# KV10BLDCControl.net
KiCad netlist of a schematic drawn in Altium Designer
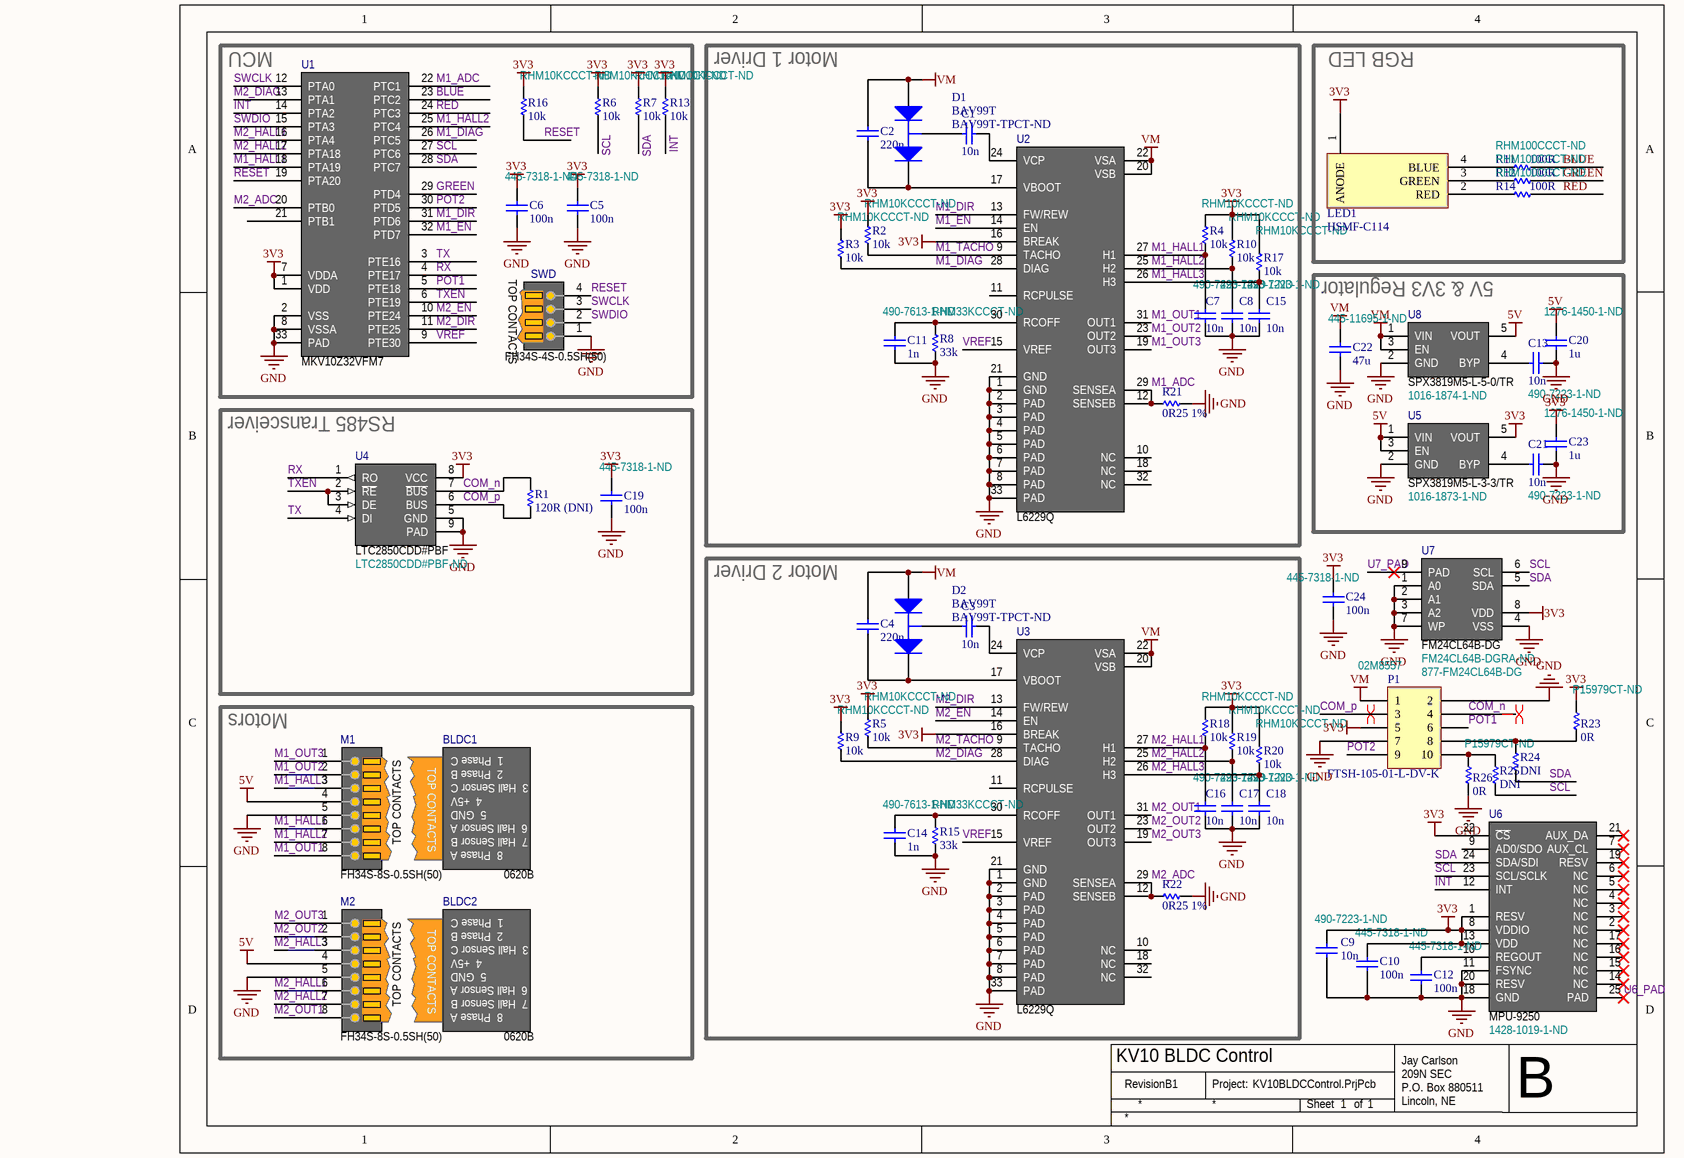
[diagram p0: KV10BLDCControl.SchDoc]

(export (version "E")
  (design (tool "Eeschema 10.0.6"))
  (components
    (comp (ref "BLDC1") (value "0620B") (libsource (lib "Faulhaber BLDC Motors") (part "0620B")))
    (comp (ref "BLDC2") (value "0620B") (libsource (lib "Faulhaber BLDC Motors") (part "0620B")))
    (comp (ref "C1")
      (value "10n")
      (footprint "CAPC1005N")
      (description "Capacitor (Semiconductor SIM Model)")
      (fields (field (name "PUBLISHER") "Altium Limited"))
      (libsource (lib "Miscellaneous Devices") (part "Cap Semi"))
    )
    (comp (ref "C2")
      (value "220n")
      (footprint "CAPC1005N")
      (description "Capacitor (Semiconductor SIM Model)")
      (fields (field (name "PUBLISHER") "Altium Limited"))
      (libsource (lib "Miscellaneous Devices") (part "Cap Semi"))
    )
    (comp (ref "C3")
      (value "10n")
      (footprint "CAPC1005N")
      (description "Capacitor (Semiconductor SIM Model)")
      (fields (field (name "PUBLISHER") "Altium Limited"))
      (libsource (lib "Miscellaneous Devices") (part "Cap Semi"))
    )
    (comp (ref "C4")
      (value "220n")
      (footprint "CAPC1005N")
      (description "Capacitor (Semiconductor SIM Model)")
      (fields (field (name "PUBLISHER") "Altium Limited"))
      (libsource (lib "Miscellaneous Devices") (part "Cap Semi"))
    )
    (comp (ref "C5")
      (value "100n")
      (footprint "CAPC0603N")
      (description "Capacitor (Semiconductor SIM Model)")
      (fields
        (field (name "SUPPLIER PART NUMBER 1") "445-7318-1-ND")
        (field (name "PUBLISHER") "Altium Limited")
      )
      (libsource (lib "Miscellaneous Devices") (part "Cap Semi"))
    )
    (comp (ref "C6")
      (value "100n")
      (footprint "CAPC0603N")
      (description "Capacitor (Semiconductor SIM Model)")
      (fields
        (field (name "SUPPLIER PART NUMBER 1") "445-7318-1-ND")
        (field (name "PUBLISHER") "Altium Limited")
      )
      (libsource (lib "Miscellaneous Devices") (part "Cap Semi"))
    )
    (comp (ref "C7")
      (value "10n")
      (footprint "CAPC0603N")
      (description "Capacitor (Semiconductor SIM Model)")
      (fields
        (field (name "SUPPLIER PART NUMBER 1") "490-7223-1-ND")
        (field (name "PUBLISHER") "Altium Limited")
      )
      (libsource (lib "Miscellaneous Devices") (part "Cap Semi"))
    )
    (comp (ref "C8")
      (value "10n")
      (footprint "CAPC0603N")
      (description "Capacitor (Semiconductor SIM Model)")
      (fields
        (field (name "SUPPLIER PART NUMBER 1") "490-7223-1-ND")
        (field (name "PUBLISHER") "Altium Limited")
      )
      (libsource (lib "Miscellaneous Devices") (part "Cap Semi"))
    )
    (comp (ref "C9")
      (value "10n")
      (footprint "CAPC0603N")
      (description "Capacitor (Semiconductor SIM Model)")
      (fields
        (field (name "SUPPLIER PART NUMBER 1") "490-7223-1-ND")
        (field (name "PUBLISHER") "Altium Limited")
      )
      (libsource (lib "Miscellaneous Devices") (part "Cap Semi"))
    )
    (comp (ref "C10")
      (value "100n")
      (footprint "CAPC0603N")
      (description "Capacitor (Semiconductor SIM Model)")
      (fields
        (field (name "SUPPLIER PART NUMBER 1") "445-7318-1-ND")
        (field (name "PUBLISHER") "Altium Limited")
      )
      (libsource (lib "Miscellaneous Devices") (part "Cap Semi"))
    )
    (comp (ref "C11")
      (value "1n")
      (footprint "CAPC0603N")
      (description "Capacitor (Semiconductor SIM Model)")
      (fields
        (field (name "SUPPLIER PART NUMBER 1") "490-7613-1-ND")
        (field (name "PUBLISHER") "Altium Limited")
      )
      (libsource (lib "Miscellaneous Devices") (part "Cap Semi"))
    )
    (comp (ref "C12")
      (value "100n")
      (footprint "CAPC0603N")
      (description "Capacitor (Semiconductor SIM Model)")
      (fields
        (field (name "SUPPLIER PART NUMBER 1") "445-7318-1-ND")
        (field (name "PUBLISHER") "Altium Limited")
      )
      (libsource (lib "Miscellaneous Devices") (part "Cap Semi"))
    )
    (comp (ref "C13")
      (value "10n")
      (footprint "CAPC0603N")
      (description "Capacitor (Semiconductor SIM Model)")
      (fields
        (field (name "SUPPLIER PART NUMBER 1") "490-7223-1-ND")
        (field (name "PUBLISHER") "Altium Limited")
      )
      (libsource (lib "Miscellaneous Devices") (part "Cap Semi"))
    )
    (comp (ref "C14")
      (value "1n")
      (footprint "CAPC0603N")
      (description "Capacitor (Semiconductor SIM Model)")
      (fields
        (field (name "SUPPLIER PART NUMBER 1") "490-7613-1-ND")
        (field (name "PUBLISHER") "Altium Limited")
      )
      (libsource (lib "Miscellaneous Devices") (part "Cap Semi"))
    )
    (comp (ref "C15")
      (value "10n")
      (footprint "CAPC0603N")
      (description "Capacitor (Semiconductor SIM Model)")
      (fields
        (field (name "SUPPLIER PART NUMBER 1") "490-7223-1-ND")
        (field (name "PUBLISHER") "Altium Limited")
      )
      (libsource (lib "Miscellaneous Devices") (part "Cap Semi"))
    )
    (comp (ref "C16")
      (value "10n")
      (footprint "CAPC0603N")
      (description "Capacitor (Semiconductor SIM Model)")
      (fields
        (field (name "SUPPLIER PART NUMBER 1") "490-7223-1-ND")
        (field (name "PUBLISHER") "Altium Limited")
      )
      (libsource (lib "Miscellaneous Devices") (part "Cap Semi"))
    )
    (comp (ref "C17")
      (value "10n")
      (footprint "CAPC0603N")
      (description "Capacitor (Semiconductor SIM Model)")
      (fields
        (field (name "SUPPLIER PART NUMBER 1") "490-7223-1-ND")
        (field (name "PUBLISHER") "Altium Limited")
      )
      (libsource (lib "Miscellaneous Devices") (part "Cap Semi"))
    )
    (comp (ref "C18")
      (value "10n")
      (footprint "CAPC0603N")
      (description "Capacitor (Semiconductor SIM Model)")
      (fields
        (field (name "SUPPLIER PART NUMBER 1") "490-7223-1-ND")
        (field (name "PUBLISHER") "Altium Limited")
      )
      (libsource (lib "Miscellaneous Devices") (part "Cap Semi"))
    )
    (comp (ref "C19")
      (value "100n")
      (footprint "CAPC0603N")
      (description "Capacitor (Semiconductor SIM Model)")
      (fields
        (field (name "SUPPLIER PART NUMBER 1") "445-7318-1-ND")
        (field (name "PUBLISHER") "Altium Limited")
      )
      (libsource (lib "Miscellaneous Devices") (part "Cap Semi"))
    )
    (comp (ref "C20")
      (value "1u")
      (footprint "CAPC1005N")
      (description "Capacitor (Semiconductor SIM Model)")
      (fields
        (field (name "SUPPLIER PART NUMBER 1") "1276-1450-1-ND")
        (field (name "PUBLISHER") "Altium Limited")
      )
      (libsource (lib "Miscellaneous Devices") (part "Cap Semi"))
    )
    (comp (ref "C21")
      (value "10n")
      (footprint "CAPC0603N")
      (description "Capacitor (Semiconductor SIM Model)")
      (fields
        (field (name "SUPPLIER PART NUMBER 1") "490-7223-1-ND")
        (field (name "PUBLISHER") "Altium Limited")
      )
      (libsource (lib "Miscellaneous Devices") (part "Cap Semi"))
    )
    (comp (ref "C22")
      (value "47u")
      (footprint "CAPC3216N")
      (description "Capacitor (Semiconductor SIM Model)")
      (fields
        (field (name "SUPPLIER PART NUMBER 1") "445-11695-1-ND")
        (field (name "PUBLISHER") "Altium Limited")
      )
      (libsource (lib "Miscellaneous Devices") (part "Cap Semi"))
    )
    (comp (ref "C23")
      (value "1u")
      (footprint "CAPC1005N")
      (description "Capacitor (Semiconductor SIM Model)")
      (fields
        (field (name "SUPPLIER PART NUMBER 1") "1276-1450-1-ND")
        (field (name "PUBLISHER") "Altium Limited")
      )
      (libsource (lib "Miscellaneous Devices") (part "Cap Semi"))
    )
    (comp (ref "C24")
      (value "100n")
      (footprint "CAPC0603N")
      (description "Capacitor (Semiconductor SIM Model)")
      (fields
        (field (name "SUPPLIER PART NUMBER 1") "445-7318-1-ND")
        (field (name "PUBLISHER") "Altium Limited")
      )
      (libsource (lib "Miscellaneous Devices") (part "Cap Semi"))
    )
    (comp (ref "D1")
      (value "BAV99T")
      (footprint "SOT-523 (SC-75)")
      (description "Silicon Switching Diode for High-Speed Switching")
      (fields
        (field (name "SUPPLIER PART NUMBER 1") "BAV99T-TPCT-ND")
        (field (name "PUBLISHER") "Altium Limited")
      )
      (libsource (lib "Infineon Discrete Diode") (part "BAV99T"))
    )
    (comp (ref "D2")
      (value "BAV99T")
      (footprint "SOT-523 (SC-75)")
      (description "Silicon Switching Diode for High-Speed Switching")
      (fields
        (field (name "SUPPLIER PART NUMBER 1") "BAV99T-TPCT-ND")
        (field (name "PUBLISHER") "Altium Limited")
      )
      (libsource (lib "Infineon Discrete Diode") (part "BAV99T"))
    )
    (comp (ref "LED1")
      (value "HSMF-C114")
      (footprint "HSMF-C114")
      (description "LED CHIP RGB 1.6X1.5X0.35MM SMD")
      (fields (field (name "MANUFACTURER") "Avago Technologies US Inc."))
      (libsource (lib "components") (part "HSMF-C114"))
    )
    (comp (ref "M1")
      (value "FH34S-8S-0.5SH(50)")
      (footprint "FH34S-8S-0.5SH(50)")
      (description "CONN FPC/FFC 8POS .5MM SMD GOLD")
      (fields (field (name "MANUFACTURER") "Hirose Electric Co Ltd"))
      (libsource (lib "FH34 series") (part "FH34S-8S-0.5SH(50)"))
    )
    (comp (ref "M2")
      (value "FH34S-8S-0.5SH(50)")
      (footprint "FH34S-8S-0.5SH(50)")
      (description "CONN FPC/FFC 8POS .5MM SMD GOLD")
      (fields (field (name "MANUFACTURER") "Hirose Electric Co Ltd"))
      (libsource (lib "FH34 series") (part "FH34S-8S-0.5SH(50)"))
    )
    (comp (ref "P1")
      (value "FTSH-105-01-L-DV-K")
      (footprint "FTSH-105-01-L-DV-K")
      (description "Header, 5-Pin, Dual row")
      (fields (field (name "SUPPLIER PART NUMBER 1") "02M8557") (field (name "PUBLISHER") "Altium Limited"))
      (libsource (lib "Miscellaneous Connectors") (part "MHDR2X5"))
    )
    (comp (ref "R1")
      (value "120R (DNI)")
      (footprint "RESC0603N")
      (description "Semiconductor Resistor")
      (fields (field (name "PUBLISHER") "Altium Limited"))
      (libsource (lib "Miscellaneous Devices") (part "Res Semi"))
    )
    (comp (ref "R2")
      (value "10k")
      (footprint "RESC0603N")
      (description "Semiconductor Resistor")
      (fields
        (field (name "SUPPLIER PART NUMBER 1") "RHM10KCCCT-ND")
        (field (name "PUBLISHER") "Altium Limited")
      )
      (libsource (lib "Miscellaneous Devices") (part "Res Semi"))
    )
    (comp (ref "R3")
      (value "10k")
      (footprint "RESC0603N")
      (description "Semiconductor Resistor")
      (fields
        (field (name "SUPPLIER PART NUMBER 1") "RHM10KCCCT-ND")
        (field (name "PUBLISHER") "Altium Limited")
      )
      (libsource (lib "Miscellaneous Devices") (part "Res Semi"))
    )
    (comp (ref "R4")
      (value "10k")
      (footprint "RESC0603N")
      (description "Semiconductor Resistor")
      (fields
        (field (name "SUPPLIER PART NUMBER 1") "RHM10KCCCT-ND")
        (field (name "PUBLISHER") "Altium Limited")
      )
      (libsource (lib "Miscellaneous Devices") (part "Res Semi"))
    )
    (comp (ref "R5")
      (value "10k")
      (footprint "RESC0603N")
      (description "Semiconductor Resistor")
      (fields
        (field (name "SUPPLIER PART NUMBER 1") "RHM10KCCCT-ND")
        (field (name "PUBLISHER") "Altium Limited")
      )
      (libsource (lib "Miscellaneous Devices") (part "Res Semi"))
    )
    (comp (ref "R6")
      (value "10k")
      (footprint "RESC0603N")
      (description "Semiconductor Resistor")
      (fields
        (field (name "SUPPLIER PART NUMBER 1") "RHM10KCCCT-ND")
        (field (name "PUBLISHER") "Altium Limited")
      )
      (libsource (lib "Miscellaneous Devices") (part "Res Semi"))
    )
    (comp (ref "R7")
      (value "10k")
      (footprint "RESC0603N")
      (description "Semiconductor Resistor")
      (fields
        (field (name "SUPPLIER PART NUMBER 1") "RHM10KCCCT-ND")
        (field (name "PUBLISHER") "Altium Limited")
      )
      (libsource (lib "Miscellaneous Devices") (part "Res Semi"))
    )
    (comp (ref "R8")
      (value "33k")
      (footprint "RESC0603N")
      (description "Semiconductor Resistor")
      (fields
        (field (name "SUPPLIER PART NUMBER 1") "RHM33KCCCT-ND")
        (field (name "PUBLISHER") "Altium Limited")
      )
      (libsource (lib "Miscellaneous Devices") (part "Res Semi"))
    )
    (comp (ref "R9")
      (value "10k")
      (footprint "RESC0603N")
      (description "Semiconductor Resistor")
      (fields
        (field (name "SUPPLIER PART NUMBER 1") "RHM10KCCCT-ND")
        (field (name "PUBLISHER") "Altium Limited")
      )
      (libsource (lib "Miscellaneous Devices") (part "Res Semi"))
    )
    (comp (ref "R10")
      (value "10k")
      (footprint "RESC0603N")
      (description "Semiconductor Resistor")
      (fields
        (field (name "SUPPLIER PART NUMBER 1") "RHM10KCCCT-ND")
        (field (name "PUBLISHER") "Altium Limited")
      )
      (libsource (lib "Miscellaneous Devices") (part "Res Semi"))
    )
    (comp (ref "R11")
      (value "100R")
      (footprint "RESC0603N")
      (description "Semiconductor Resistor")
      (fields
        (field (name "SUPPLIER PART NUMBER 1") "RHM100CCCT-ND")
        (field (name "PUBLISHER") "Altium Limited")
      )
      (libsource (lib "Miscellaneous Devices") (part "Res Semi"))
    )
    (comp (ref "R12")
      (value "100R")
      (footprint "RESC0603N")
      (description "Semiconductor Resistor")
      (fields
        (field (name "SUPPLIER PART NUMBER 1") "RHM100CCCT-ND")
        (field (name "PUBLISHER") "Altium Limited")
      )
      (libsource (lib "Miscellaneous Devices") (part "Res Semi"))
    )
    (comp (ref "R13")
      (value "10k")
      (footprint "RESC0603N")
      (description "Semiconductor Resistor")
      (fields
        (field (name "SUPPLIER PART NUMBER 1") "RHM10KCCCT-ND")
        (field (name "PUBLISHER") "Altium Limited")
      )
      (libsource (lib "Miscellaneous Devices") (part "Res Semi"))
    )
    (comp (ref "R14")
      (value "100R")
      (footprint "RESC0603N")
      (description "Semiconductor Resistor")
      (fields
        (field (name "SUPPLIER PART NUMBER 1") "RHM100CCCT-ND")
        (field (name "PUBLISHER") "Altium Limited")
      )
      (libsource (lib "Miscellaneous Devices") (part "Res Semi"))
    )
    (comp (ref "R15")
      (value "33k")
      (footprint "RESC0603N")
      (description "Semiconductor Resistor")
      (fields
        (field (name "SUPPLIER PART NUMBER 1") "RHM33KCCCT-ND")
        (field (name "PUBLISHER") "Altium Limited")
      )
      (libsource (lib "Miscellaneous Devices") (part "Res Semi"))
    )
    (comp (ref "R16")
      (value "10k")
      (footprint "RESC0603N")
      (description "Semiconductor Resistor")
      (fields
        (field (name "SUPPLIER PART NUMBER 1") "RHM10KCCCT-ND")
        (field (name "PUBLISHER") "Altium Limited")
      )
      (libsource (lib "Miscellaneous Devices") (part "Res Semi"))
    )
    (comp (ref "R17")
      (value "10k")
      (footprint "RESC0603N")
      (description "Semiconductor Resistor")
      (fields
        (field (name "SUPPLIER PART NUMBER 1") "RHM10KCCCT-ND")
        (field (name "PUBLISHER") "Altium Limited")
      )
      (libsource (lib "Miscellaneous Devices") (part "Res Semi"))
    )
    (comp (ref "R18")
      (value "10k")
      (footprint "RESC0603N")
      (description "Semiconductor Resistor")
      (fields
        (field (name "SUPPLIER PART NUMBER 1") "RHM10KCCCT-ND")
        (field (name "PUBLISHER") "Altium Limited")
      )
      (libsource (lib "Miscellaneous Devices") (part "Res Semi"))
    )
    (comp (ref "R19")
      (value "10k")
      (footprint "RESC0603N")
      (description "Semiconductor Resistor")
      (fields
        (field (name "SUPPLIER PART NUMBER 1") "RHM10KCCCT-ND")
        (field (name "PUBLISHER") "Altium Limited")
      )
      (libsource (lib "Miscellaneous Devices") (part "Res Semi"))
    )
    (comp (ref "R20")
      (value "10k")
      (footprint "RESC0603N")
      (description "Semiconductor Resistor")
      (fields
        (field (name "SUPPLIER PART NUMBER 1") "RHM10KCCCT-ND")
        (field (name "PUBLISHER") "Altium Limited")
      )
      (libsource (lib "Miscellaneous Devices") (part "Res Semi"))
    )
    (comp (ref "R21")
      (value "0R25 1%")
      (footprint "RESC1608N")
      (description "Semiconductor Resistor")
      (fields (field (name "PUBLISHER") "Altium Limited"))
      (libsource (lib "Miscellaneous Devices") (part "Res Semi"))
    )
    (comp (ref "R22")
      (value "0R25 1%")
      (footprint "RESC1608N")
      (description "Semiconductor Resistor")
      (fields (field (name "PUBLISHER") "Altium Limited"))
      (libsource (lib "Miscellaneous Devices") (part "Res Semi"))
    )
    (comp (ref "R23")
      (value "0R")
      (footprint "RESC0603N")
      (description "Semiconductor Resistor")
      (fields
        (field (name "SUPPLIER PART NUMBER 1") "P15979CT-ND")
        (field (name "PUBLISHER") "Altium Limited")
      )
      (libsource (lib "Miscellaneous Devices") (part "Res Semi"))
    )
    (comp (ref "R24")
      (value "DNI")
      (footprint "RESC0603N")
      (description "Semiconductor Resistor")
      (fields (field (name "PUBLISHER") "Altium Limited"))
      (libsource (lib "Miscellaneous Devices") (part "Res Semi"))
    )
    (comp (ref "R25")
      (value "DNI")
      (footprint "RESC0603N")
      (description "Semiconductor Resistor")
      (fields (field (name "PUBLISHER") "Altium Limited"))
      (libsource (lib "Miscellaneous Devices") (part "Res Semi"))
    )
    (comp (ref "R26")
      (value "0R")
      (footprint "RESC0603N")
      (description "Semiconductor Resistor")
      (fields
        (field (name "SUPPLIER PART NUMBER 1") "P15979CT-ND")
        (field (name "PUBLISHER") "Altium Limited")
      )
      (libsource (lib "Miscellaneous Devices") (part "Res Semi"))
    )
    (comp (ref "SWD")
      (value "FH34S-4S-0.5SH(50)")
      (footprint "FH34S-4S-0.5SH(50)")
      (description "CONN FPC/FFC 4POS .5MM SMD GOLD")
      (fields (field (name "MANUFACTURER") "Hirose Electric Co Ltd"))
      (libsource (lib "FH34 series") (part "FH34S-4S-0.5SH(50)"))
    )
    (comp (ref "U1")
      (value "MKV10Z32VFM7")
      (footprint "QFN50P500X500-32V2N")
      (description "Kinetis Cortex-M0+75 MHz Motor Control 32QFN")
      (fields (field (name "MANUFACTURER") "Freescale Semiconductor"))
      (libsource (lib "Freescale K-Series ARM Microcontroller") (part "MKV10Z32VFM7"))
    )
    (comp (ref "U2")
      (value "L6229Q")
      (description "IC MOTOR DRIVER PAR 32VFQFPN")
      (fields
        (field (name "MANUFACTURER") "STMicroelectronics")
        (field (name "MANUFACTURER PART NUMBER") "L6229QTR")
      )
      (libsource (lib "ST Motor Driver") (part "L6229Q"))
    )
    (comp (ref "U3")
      (value "L6229Q")
      (description "IC MOTOR DRIVER PAR 32VFQFPN")
      (fields
        (field (name "MANUFACTURER") "STMicroelectronics")
        (field (name "MANUFACTURER PART NUMBER") "L6229QTR")
      )
      (libsource (lib "ST Motor Driver") (part "L6229Q"))
    )
    (comp (ref "U4")
      (value "LTC2850CDD#PBF")
      (footprint "DFN50P300X300X75-8N")
      (description "IC TXRX RS485 20MBPS 8-DFN")
      (fields
        (field (name "MANUFACTURER") "Linear Technology")
        (field (name "MANUFACTURER PART NUMBER") "LTC2850CMS8#PBF")
        (field (name "SUPPLIER PART NUMBER 1") "LTC2850CDD#PBF-ND")
      )
      (libsource (lib "LTC Transceiver") (part "LTC2850CDD#PBF"))
    )
    (comp (ref "U5")
      (value "SPX3819M5-L-3-3/TR")
      (footprint "SOT23-5AN")
      (description "IC REG LDO 3.3V 0.5A SOT23-5")
      (fields
        (field (name "MANUFACTURER") "Exar Corporation")
        (field (name "SUPPLIER PART NUMBER 1") "1016-1873-1-ND")
      )
      (libsource (lib "Exar LDO Regulator") (part "SPX3819M5-L-3-3/TR"))
    )
    (comp (ref "U6")
      (value "MPU-9250")
      (footprint "QFN40P300X300X105_HS-25N")
      (description "GYRO/ACCEL/COMPASS/9-AXIS")
      (fields
        (field (name "MANUFACTURER") "InvenSense")
        (field (name "SUPPLIER PART NUMBER 1") "1428-1019-1-ND")
      )
      (libsource (lib "Invensense MPU") (part "MPU-9250"))
    )
    (comp (ref "U7")
      (value "FM24CL64B-DG")
      (footprint "DFN95P400X445X80_HS-9N")
      (description "IC FRAM 64KBIT 1MHZ 8TDFN")
      (fields
        (field (name "MANUFACTURER") "Cypress Semiconductor Corp")
        (field (name "SUPPLIER PART NUMBER 1") "FM24CL64B-DGRA-ND")
        (field (name "SUPPLIER PART NUMBER 2") "877-FM24CL64B-DG")
      )
      (libsource (lib "Cypress FRAM") (part "FM24CL64B-DG"))
    )
    (comp (ref "U8")
      (value "SPX3819M5-L-5-0/TR")
      (footprint "SOT23-5AN")
      (description "IC REG LDO 5V 0.5A SOT23-5")
      (fields
        (field (name "MANUFACTURER") "Exar Corporation")
        (field (name "SUPPLIER PART NUMBER 1") "1016-1874-1-ND")
      )
      (libsource (lib "Exar LDO Regulator") (part "SPX3819M5-L-5-0/TR"))
    )
  )
  (nets
    (net (code "1") (name "/BLUE") (class "Default")
      (node (ref "R11") (pin "1") (pinfunction "1_1") (pintype "passive"))
      (node (ref "U1") (pin "23") (pinfunction "PTC2_23") (pintype "passive"))
    )
    (net (code "2") (name "/COM_n") (class "Default")
      (node (ref "P1") (pin "4") (pinfunction "4_4") (pintype "passive"))
      (node (ref "R1") (pin "2") (pinfunction "2_2") (pintype "passive"))
      (node (ref "U4") (pin "7") (pinfunction "~{BUS}_7") (pintype "power_in"))
    )
    (net (code "3") (name "/COM_p") (class "Default")
      (node (ref "P1") (pin "3") (pinfunction "3_3") (pintype "passive"))
      (node (ref "R1") (pin "1") (pinfunction "1_1") (pintype "passive"))
      (node (ref "U4") (pin "6") (pinfunction "BUS_6") (pintype "power_in"))
    )
    (net (code "4") (name "/GREEN") (class "Default")
      (node (ref "R12") (pin "1") (pinfunction "1_1") (pintype "passive"))
      (node (ref "U1") (pin "29") (pinfunction "PTD4_29") (pintype "passive"))
    )
    (net (code "5") (name "/INT") (class "Default")
      (node (ref "R13") (pin "1") (pinfunction "1_1") (pintype "passive"))
      (node (ref "U1") (pin "14") (pinfunction "PTA2_14") (pintype "passive"))
      (node (ref "U6") (pin "12") (pinfunction "INT_12") (pintype "power_in"))
    )
    (net (code "6") (name "/M1_ADC") (class "Default")
      (node (ref "R21") (pin "2") (pinfunction "2_2") (pintype "passive"))
      (node (ref "U1") (pin "22") (pinfunction "PTC1_22") (pintype "passive"))
      (node (ref "U2") (pin "12") (pinfunction "SENSEB_12") (pintype "passive"))
      (node (ref "U2") (pin "29") (pinfunction "SENSEA_29") (pintype "passive"))
    )
    (net (code "7") (name "/M1_DIAG") (class "Default")
      (node (ref "R3") (pin "2") (pinfunction "2_2") (pintype "passive"))
      (node (ref "U1") (pin "26") (pinfunction "PTC5_26") (pintype "passive"))
      (node (ref "U2") (pin "28") (pinfunction "DIAG_28") (pintype "passive"))
    )
    (net (code "8") (name "/M1_DIR") (class "Default")
      (node (ref "U1") (pin "31") (pinfunction "PTD6_31") (pintype "passive"))
      (node (ref "U2") (pin "13") (pinfunction "FW/REW_13") (pintype "passive"))
    )
    (net (code "9") (name "/M1_EN") (class "Default")
      (node (ref "U1") (pin "32") (pinfunction "PTD7_32") (pintype "passive"))
      (node (ref "U2") (pin "14") (pinfunction "EN_14") (pintype "passive"))
    )
    (net (code "10") (name "/M1_HALL1") (class "Default")
      (node (ref "C7") (pin "2") (pinfunction "2_2") (pintype "passive"))
      (node (ref "M1") (pin "6") (pinfunction "6_6") (pintype "passive"))
      (node (ref "R4") (pin "1") (pinfunction "1_1") (pintype "passive"))
      (node (ref "U1") (pin "18") (pinfunction "PTA19_18") (pintype "passive"))
      (node (ref "U2") (pin "27") (pinfunction "H1_27") (pintype "passive"))
    )
    (net (code "11") (name "/M1_HALL2") (class "Default")
      (node (ref "C8") (pin "2") (pinfunction "2_2") (pintype "passive"))
      (node (ref "M1") (pin "7") (pinfunction "7_7") (pintype "passive"))
      (node (ref "R10") (pin "1") (pinfunction "1_1") (pintype "passive"))
      (node (ref "U1") (pin "25") (pinfunction "PTC4_25") (pintype "passive"))
      (node (ref "U2") (pin "25") (pinfunction "H2_25") (pintype "passive"))
    )
    (net (code "12") (name "/M1_HALL3") (class "Default")
      (node (ref "C15") (pin "2") (pinfunction "2_2") (pintype "passive"))
      (node (ref "M1") (pin "3") (pinfunction "3_3") (pintype "passive"))
      (node (ref "R17") (pin "1") (pinfunction "1_1") (pintype "passive"))
      (node (ref "U2") (pin "26") (pinfunction "H3_26") (pintype "passive"))
    )
    (net (code "13") (name "/M1_OUT1") (class "Default")
      (node (ref "M1") (pin "8") (pinfunction "8_8") (pintype "passive"))
      (node (ref "U2") (pin "31") (pinfunction "OUT1_31") (pintype "passive"))
    )
    (net (code "14") (name "/M1_OUT2") (class "Default")
      (node (ref "M1") (pin "2") (pinfunction "2_2") (pintype "passive"))
      (node (ref "U2") (pin "23") (pinfunction "OUT2_23") (pintype "passive"))
    )
    (net (code "15") (name "/M1_OUT3") (class "Default")
      (node (ref "M1") (pin "1") (pinfunction "1_1") (pintype "passive"))
      (node (ref "U2") (pin "19") (pinfunction "OUT3_19") (pintype "passive"))
    )
    (net (code "16") (name "/M1_TACHO") (class "Default")
      (node (ref "R2") (pin "2") (pinfunction "2_2") (pintype "passive"))
      (node (ref "U2") (pin "9") (pinfunction "TACHO_9") (pintype "passive"))
    )
    (net (code "17") (name "/M2_ADC") (class "Default")
      (node (ref "R22") (pin "2") (pinfunction "2_2") (pintype "passive"))
      (node (ref "U1") (pin "20") (pinfunction "PTB0_20") (pintype "passive"))
      (node (ref "U3") (pin "12") (pinfunction "SENSEB_12") (pintype "passive"))
      (node (ref "U3") (pin "29") (pinfunction "SENSEA_29") (pintype "passive"))
    )
    (net (code "18") (name "/M2_DIAG") (class "Default")
      (node (ref "R9") (pin "2") (pinfunction "2_2") (pintype "passive"))
      (node (ref "U1") (pin "13") (pinfunction "PTA1_13") (pintype "passive"))
      (node (ref "U3") (pin "28") (pinfunction "DIAG_28") (pintype "passive"))
    )
    (net (code "19") (name "/M2_DIR") (class "Default")
      (node (ref "U1") (pin "11") (pinfunction "PTE25_11") (pintype "passive"))
      (node (ref "U3") (pin "13") (pinfunction "FW/REW_13") (pintype "passive"))
    )
    (net (code "20") (name "/M2_EN") (class "Default")
      (node (ref "U1") (pin "10") (pinfunction "PTE24_10") (pintype "passive"))
      (node (ref "U3") (pin "14") (pinfunction "EN_14") (pintype "passive"))
    )
    (net (code "21") (name "/M2_HALL1") (class "Default")
      (node (ref "C16") (pin "2") (pinfunction "2_2") (pintype "passive"))
      (node (ref "M2") (pin "6") (pinfunction "6_6") (pintype "passive"))
      (node (ref "R18") (pin "1") (pinfunction "1_1") (pintype "passive"))
      (node (ref "U1") (pin "16") (pinfunction "PTA4_16") (pintype "passive"))
      (node (ref "U3") (pin "27") (pinfunction "H1_27") (pintype "passive"))
    )
    (net (code "22") (name "/M2_HALL2") (class "Default")
      (node (ref "C17") (pin "2") (pinfunction "2_2") (pintype "passive"))
      (node (ref "M2") (pin "7") (pinfunction "7_7") (pintype "passive"))
      (node (ref "R19") (pin "1") (pinfunction "1_1") (pintype "passive"))
      (node (ref "U1") (pin "17") (pinfunction "PTA18_17") (pintype "passive"))
      (node (ref "U3") (pin "25") (pinfunction "H2_25") (pintype "passive"))
    )
    (net (code "23") (name "/M2_HALL3") (class "Default")
      (node (ref "C18") (pin "2") (pinfunction "2_2") (pintype "passive"))
      (node (ref "M2") (pin "3") (pinfunction "3_3") (pintype "passive"))
      (node (ref "R20") (pin "1") (pinfunction "1_1") (pintype "passive"))
      (node (ref "U3") (pin "26") (pinfunction "H3_26") (pintype "passive"))
    )
    (net (code "24") (name "/M2_OUT1") (class "Default")
      (node (ref "M2") (pin "8") (pinfunction "8_8") (pintype "passive"))
      (node (ref "U3") (pin "31") (pinfunction "OUT1_31") (pintype "passive"))
    )
    (net (code "25") (name "/M2_OUT2") (class "Default")
      (node (ref "M2") (pin "2") (pinfunction "2_2") (pintype "passive"))
      (node (ref "U3") (pin "23") (pinfunction "OUT2_23") (pintype "passive"))
    )
    (net (code "26") (name "/M2_OUT3") (class "Default")
      (node (ref "M2") (pin "1") (pinfunction "1_1") (pintype "passive"))
      (node (ref "U3") (pin "19") (pinfunction "OUT3_19") (pintype "passive"))
    )
    (net (code "27") (name "/M2_TACHO") (class "Default")
      (node (ref "R5") (pin "2") (pinfunction "2_2") (pintype "passive"))
      (node (ref "U3") (pin "9") (pinfunction "TACHO_9") (pintype "passive"))
    )
    (net (code "28") (name "/POT1") (class "Default")
      (node (ref "P1") (pin "6") (pinfunction "6_6") (pintype "passive"))
      (node (ref "U1") (pin "5") (pinfunction "PTE18_5") (pintype "passive"))
    )
    (net (code "29") (name "/POT2") (class "Default")
      (node (ref "P1") (pin "9") (pinfunction "9_9") (pintype "passive"))
      (node (ref "U1") (pin "30") (pinfunction "PTD5_30") (pintype "passive"))
    )
    (net (code "30") (name "/RED") (class "Default")
      (node (ref "R14") (pin "1") (pinfunction "1_1") (pintype "passive"))
      (node (ref "U1") (pin "24") (pinfunction "PTC3_24") (pintype "passive"))
    )
    (net (code "31") (name "/RESET") (class "Default")
      (node (ref "R16") (pin "1") (pinfunction "1_1") (pintype "passive"))
      (node (ref "SWD") (pin "4") (pinfunction "4_4") (pintype "passive"))
      (node (ref "U1") (pin "19") (pinfunction "PTA20_19") (pintype "passive"))
    )
    (net (code "32") (name "/RX") (class "Default")
      (node (ref "U1") (pin "4") (pinfunction "PTE17_4") (pintype "passive"))
      (node (ref "U4") (pin "1") (pinfunction "RO_1") (pintype "output"))
    )
    (net (code "33") (name "/SCL") (class "Default")
      (node (ref "R25") (pin "2") (pinfunction "2_2") (pintype "passive"))
      (node (ref "R6") (pin "1") (pinfunction "1_1") (pintype "passive"))
      (node (ref "U1") (pin "27") (pinfunction "PTC6_27") (pintype "passive"))
      (node (ref "U6") (pin "23") (pinfunction "SCL/SCLK_23") (pintype "power_in"))
      (node (ref "U7") (pin "6") (pinfunction "SCL_6") (pintype "power_in"))
    )
    (net (code "34") (name "/SDA") (class "Default")
      (node (ref "R24") (pin "2") (pinfunction "2_2") (pintype "passive"))
      (node (ref "R7") (pin "1") (pinfunction "1_1") (pintype "passive"))
      (node (ref "U1") (pin "28") (pinfunction "PTC7_28") (pintype "passive"))
      (node (ref "U6") (pin "24") (pinfunction "SDA/SDI_24") (pintype "power_in"))
      (node (ref "U7") (pin "5") (pinfunction "SDA_5") (pintype "power_in"))
    )
    (net (code "35") (name "/SWCLK") (class "Default")
      (node (ref "SWD") (pin "3") (pinfunction "3_3") (pintype "passive"))
      (node (ref "U1") (pin "12") (pinfunction "PTA0_12") (pintype "passive"))
    )
    (net (code "36") (name "/SWDIO") (class "Default")
      (node (ref "SWD") (pin "2") (pinfunction "2_2") (pintype "passive"))
      (node (ref "U1") (pin "15") (pinfunction "PTA3_15") (pintype "passive"))
    )
    (net (code "37") (name "/TX") (class "Default")
      (node (ref "U1") (pin "3") (pinfunction "PTE16_3") (pintype "passive"))
      (node (ref "U4") (pin "4") (pinfunction "DI_4") (pintype "input"))
    )
    (net (code "38") (name "/TXEN") (class "Default")
      (node (ref "U1") (pin "6") (pinfunction "PTE19_6") (pintype "passive"))
      (node (ref "U4") (pin "2") (pinfunction "~{RE}_2") (pintype "input"))
      (node (ref "U4") (pin "3") (pinfunction "DE_3") (pintype "input"))
    )
    (net (code "39") (name "/U6_PAD") (class "Default")
      (node (ref "U6") (pin "25") (pinfunction "PAD_25") (pintype "power_in+no_connect"))
    )
    (net (code "40") (name "/U7_PAD") (class "Default")
      (node (ref "U7") (pin "9") (pinfunction "PAD_9") (pintype "power_in+no_connect"))
    )
    (net (code "41") (name "/VREF") (class "Default")
      (node (ref "U1") (pin "9") (pinfunction "PTE30_9") (pintype "passive"))
      (node (ref "U2") (pin "15") (pinfunction "VREF_15") (pintype "passive"))
      (node (ref "U3") (pin "15") (pinfunction "VREF_15") (pintype "passive"))
    )
    (net (code "42") (name "3V3") (class "Default")
      (node (ref "C10") (pin "2") (pinfunction "2_2") (pintype "passive"))
      (node (ref "C19") (pin "2") (pinfunction "2_2") (pintype "passive"))
      (node (ref "C23") (pin "2") (pinfunction "2_2") (pintype "passive"))
      (node (ref "C24") (pin "2") (pinfunction "2_2") (pintype "passive"))
      (node (ref "C5") (pin "2") (pinfunction "2_2") (pintype "passive"))
      (node (ref "C6") (pin "2") (pinfunction "2_2") (pintype "passive"))
      (node (ref "C9") (pin "2") (pinfunction "2_2") (pintype "passive"))
      (node (ref "LED1") (pin "1") (pinfunction "ANODE_1") (pintype "passive"))
      (node (ref "P1") (pin "5") (pinfunction "5_5") (pintype "passive"))
      (node (ref "R10") (pin "2") (pinfunction "2_2") (pintype "passive"))
      (node (ref "R13") (pin "2") (pinfunction "2_2") (pintype "passive"))
      (node (ref "R16") (pin "2") (pinfunction "2_2") (pintype "passive"))
      (node (ref "R17") (pin "2") (pinfunction "2_2") (pintype "passive"))
      (node (ref "R18") (pin "2") (pinfunction "2_2") (pintype "passive"))
      (node (ref "R19") (pin "2") (pinfunction "2_2") (pintype "passive"))
      (node (ref "R2") (pin "1") (pinfunction "1_1") (pintype "passive"))
      (node (ref "R20") (pin "2") (pinfunction "2_2") (pintype "passive"))
      (node (ref "R23") (pin "2") (pinfunction "2_2") (pintype "passive"))
      (node (ref "R3") (pin "1") (pinfunction "1_1") (pintype "passive"))
      (node (ref "R4") (pin "2") (pinfunction "2_2") (pintype "passive"))
      (node (ref "R5") (pin "1") (pinfunction "1_1") (pintype "passive"))
      (node (ref "R6") (pin "2") (pinfunction "2_2") (pintype "passive"))
      (node (ref "R7") (pin "2") (pinfunction "2_2") (pintype "passive"))
      (node (ref "R9") (pin "1") (pinfunction "1_1") (pintype "passive"))
      (node (ref "U1") (pin "1") (pinfunction "VDD_1") (pintype "passive"))
      (node (ref "U1") (pin "7") (pinfunction "VDDA_7") (pintype "passive"))
      (node (ref "U2") (pin "16") (pinfunction "BREAK_16") (pintype "passive"))
      (node (ref "U3") (pin "16") (pinfunction "BREAK_16") (pintype "passive"))
      (node (ref "U4") (pin "8") (pinfunction "VCC_8") (pintype "power_in"))
      (node (ref "U5") (pin "5") (pinfunction "VOUT_5") (pintype "power_in"))
      (node (ref "U6") (pin "1") (pinfunction "RESV_1") (pintype "power_in"))
      (node (ref "U6") (pin "13") (pinfunction "VDD_13") (pintype "power_in"))
      (node (ref "U6") (pin "22") (pinfunction "~{CS}_22") (pintype "power_in"))
      (node (ref "U6") (pin "8") (pinfunction "VDDIO_8") (pintype "power_in"))
      (node (ref "U7") (pin "8") (pinfunction "VDD_8") (pintype "power_in"))
    )
    (net (code "43") (name "5V") (class "Default")
      (node (ref "C20") (pin "2") (pinfunction "2_2") (pintype "passive"))
      (node (ref "M1") (pin "4") (pinfunction "4_4") (pintype "passive"))
      (node (ref "M2") (pin "4") (pinfunction "4_4") (pintype "passive"))
      (node (ref "U5") (pin "1") (pinfunction "VIN_1") (pintype "power_in"))
      (node (ref "U5") (pin "3") (pinfunction "EN_3") (pintype "power_in"))
      (node (ref "U8") (pin "5") (pinfunction "VOUT_5") (pintype "power_in"))
    )
    (net (code "44") (name "GND") (class "Default")
      (node (ref "C10") (pin "1") (pinfunction "1_1") (pintype "passive"))
      (node (ref "C11") (pin "1") (pinfunction "1_1") (pintype "passive"))
      (node (ref "C12") (pin "1") (pinfunction "1_1") (pintype "passive"))
      (node (ref "C13") (pin "1") (pinfunction "1_1") (pintype "passive"))
      (node (ref "C14") (pin "1") (pinfunction "1_1") (pintype "passive"))
      (node (ref "C15") (pin "1") (pinfunction "1_1") (pintype "passive"))
      (node (ref "C16") (pin "1") (pinfunction "1_1") (pintype "passive"))
      (node (ref "C17") (pin "1") (pinfunction "1_1") (pintype "passive"))
      (node (ref "C18") (pin "1") (pinfunction "1_1") (pintype "passive"))
      (node (ref "C19") (pin "1") (pinfunction "1_1") (pintype "passive"))
      (node (ref "C20") (pin "1") (pinfunction "1_1") (pintype "passive"))
      (node (ref "C21") (pin "1") (pinfunction "1_1") (pintype "passive"))
      (node (ref "C22") (pin "1") (pinfunction "1_1") (pintype "passive"))
      (node (ref "C23") (pin "1") (pinfunction "1_1") (pintype "passive"))
      (node (ref "C24") (pin "1") (pinfunction "1_1") (pintype "passive"))
      (node (ref "C5") (pin "1") (pinfunction "1_1") (pintype "passive"))
      (node (ref "C6") (pin "1") (pinfunction "1_1") (pintype "passive"))
      (node (ref "C7") (pin "1") (pinfunction "1_1") (pintype "passive"))
      (node (ref "C8") (pin "1") (pinfunction "1_1") (pintype "passive"))
      (node (ref "C9") (pin "1") (pinfunction "1_1") (pintype "passive"))
      (node (ref "M1") (pin "5") (pinfunction "5_5") (pintype "passive"))
      (node (ref "M2") (pin "5") (pinfunction "5_5") (pintype "passive"))
      (node (ref "P1") (pin "2") (pinfunction "2_2") (pintype "passive"))
      (node (ref "P1") (pin "7") (pinfunction "7_7") (pintype "passive"))
      (node (ref "R15") (pin "1") (pinfunction "1_1") (pintype "passive"))
      (node (ref "R21") (pin "1") (pinfunction "1_1") (pintype "passive"))
      (node (ref "R22") (pin "1") (pinfunction "1_1") (pintype "passive"))
      (node (ref "R26") (pin "1") (pinfunction "1_1") (pintype "passive"))
      (node (ref "R8") (pin "1") (pinfunction "1_1") (pintype "passive"))
      (node (ref "SWD") (pin "1") (pinfunction "1_1") (pintype "passive"))
      (node (ref "U1") (pin "2") (pinfunction "VSS_2") (pintype "passive"))
      (node (ref "U1") (pin "33") (pinfunction "PAD_33") (pintype "passive"))
      (node (ref "U1") (pin "8") (pinfunction "VSSA_8") (pintype "passive"))
      (node (ref "U2") (pin "1") (pinfunction "GND_1") (pintype "passive"))
      (node (ref "U2") (pin "2") (pinfunction "PAD_2") (pintype "passive"))
      (node (ref "U2") (pin "21") (pinfunction "GND_21") (pintype "passive"))
      (node (ref "U2") (pin "3") (pinfunction "PAD_3") (pintype "passive"))
      (node (ref "U2") (pin "33") (pinfunction "PAD_33") (pintype "passive"))
      (node (ref "U2") (pin "4") (pinfunction "PAD_4") (pintype "passive"))
      (node (ref "U2") (pin "5") (pinfunction "PAD_5") (pintype "passive"))
      (node (ref "U2") (pin "6") (pinfunction "PAD_6") (pintype "passive"))
      (node (ref "U2") (pin "7") (pinfunction "PAD_7") (pintype "passive"))
      (node (ref "U2") (pin "8") (pinfunction "PAD_8") (pintype "passive"))
      (node (ref "U3") (pin "1") (pinfunction "GND_1") (pintype "passive"))
      (node (ref "U3") (pin "2") (pinfunction "PAD_2") (pintype "passive"))
      (node (ref "U3") (pin "21") (pinfunction "GND_21") (pintype "passive"))
      (node (ref "U3") (pin "3") (pinfunction "PAD_3") (pintype "passive"))
      (node (ref "U3") (pin "33") (pinfunction "PAD_33") (pintype "passive"))
      (node (ref "U3") (pin "4") (pinfunction "PAD_4") (pintype "passive"))
      (node (ref "U3") (pin "5") (pinfunction "PAD_5") (pintype "passive"))
      (node (ref "U3") (pin "6") (pinfunction "PAD_6") (pintype "passive"))
      (node (ref "U3") (pin "7") (pinfunction "PAD_7") (pintype "passive"))
      (node (ref "U3") (pin "8") (pinfunction "PAD_8") (pintype "passive"))
      (node (ref "U4") (pin "5") (pinfunction "GND_5") (pintype "power_in"))
      (node (ref "U4") (pin "9") (pinfunction "PAD_9") (pintype "power_in"))
      (node (ref "U5") (pin "2") (pinfunction "GND_2") (pintype "power_in"))
      (node (ref "U6") (pin "11") (pinfunction "FSYNC_11") (pintype "power_in"))
      (node (ref "U6") (pin "18") (pinfunction "GND_18") (pintype "power_in"))
      (node (ref "U6") (pin "20") (pinfunction "RESV_20") (pintype "power_in"))
      (node (ref "U7") (pin "1") (pinfunction "A0_1") (pintype "power_in"))
      (node (ref "U7") (pin "2") (pinfunction "A1_2") (pintype "power_in"))
      (node (ref "U7") (pin "3") (pinfunction "A2_3") (pintype "power_in"))
      (node (ref "U7") (pin "4") (pinfunction "VSS_4") (pintype "power_in"))
      (node (ref "U7") (pin "7") (pinfunction "WP_7") (pintype "power_in"))
      (node (ref "U8") (pin "2") (pinfunction "GND_2") (pintype "power_in"))
    )
    (net (code "45") (name "Net-(D1-C)") (class "Default")
      (node (ref "C1") (pin "1") (pinfunction "1_1") (pintype "passive"))
      (node (ref "D1") (pin "3") (pinfunction "C_3") (pintype "passive"))
    )
    (net (code "46") (name "Net-(D1-K)") (class "Default")
      (node (ref "C2") (pin "1") (pinfunction "1_1") (pintype "passive"))
      (node (ref "D1") (pin "2") (pinfunction "K_2") (pintype "passive"))
      (node (ref "U2") (pin "17") (pinfunction "VBOOT_17") (pintype "passive"))
    )
    (net (code "47") (name "Net-(D2-C)") (class "Default")
      (node (ref "C3") (pin "1") (pinfunction "1_1") (pintype "passive"))
      (node (ref "D2") (pin "3") (pinfunction "C_3") (pintype "passive"))
    )
    (net (code "48") (name "Net-(D2-K)") (class "Default")
      (node (ref "C4") (pin "1") (pinfunction "1_1") (pintype "passive"))
      (node (ref "D2") (pin "2") (pinfunction "K_2") (pintype "passive"))
      (node (ref "U3") (pin "17") (pinfunction "VBOOT_17") (pintype "passive"))
    )
    (net (code "49") (name "Net-(LED1-BLUE)") (class "Default")
      (node (ref "LED1") (pin "4") (pinfunction "BLUE_4") (pintype "passive"))
      (node (ref "R11") (pin "2") (pinfunction "2_2") (pintype "passive"))
    )
    (net (code "50") (name "Net-(LED1-GREEN)") (class "Default")
      (node (ref "LED1") (pin "3") (pinfunction "GREEN_3") (pintype "passive"))
      (node (ref "R12") (pin "2") (pinfunction "2_2") (pintype "passive"))
    )
    (net (code "51") (name "Net-(LED1-RED)") (class "Default")
      (node (ref "LED1") (pin "2") (pinfunction "RED_2") (pintype "passive"))
      (node (ref "R14") (pin "2") (pinfunction "2_2") (pintype "passive"))
    )
    (net (code "52") (name "Net-(P1-Pad8)") (class "Default")
      (node (ref "P1") (pin "8") (pinfunction "8_8") (pintype "passive"))
      (node (ref "R23") (pin "1") (pinfunction "1_1") (pintype "passive"))
      (node (ref "R24") (pin "1") (pinfunction "1_1") (pintype "passive"))
    )
    (net (code "53") (name "Net-(P1-Pad10)") (class "Default")
      (node (ref "P1") (pin "10") (pinfunction "10_10") (pintype "passive"))
      (node (ref "R25") (pin "1") (pinfunction "1_1") (pintype "passive"))
      (node (ref "R26") (pin "2") (pinfunction "2_2") (pintype "passive"))
    )
    (net (code "54") (name "Net-(U2-RCOFF)") (class "Default")
      (node (ref "C11") (pin "2") (pinfunction "2_2") (pintype "passive"))
      (node (ref "R8") (pin "2") (pinfunction "2_2") (pintype "passive"))
      (node (ref "U2") (pin "30") (pinfunction "RCOFF_30") (pintype "passive"))
    )
    (net (code "55") (name "Net-(U2-VCP)") (class "Default")
      (node (ref "C1") (pin "2") (pinfunction "2_2") (pintype "passive"))
      (node (ref "U2") (pin "24") (pinfunction "VCP_24") (pintype "passive"))
    )
    (net (code "56") (name "Net-(U3-RCOFF)") (class "Default")
      (node (ref "C14") (pin "2") (pinfunction "2_2") (pintype "passive"))
      (node (ref "R15") (pin "2") (pinfunction "2_2") (pintype "passive"))
      (node (ref "U3") (pin "30") (pinfunction "RCOFF_30") (pintype "passive"))
    )
    (net (code "57") (name "Net-(U3-VCP)") (class "Default")
      (node (ref "C3") (pin "2") (pinfunction "2_2") (pintype "passive"))
      (node (ref "U3") (pin "24") (pinfunction "VCP_24") (pintype "passive"))
    )
    (net (code "58") (name "Net-(U5-BYP)") (class "Default")
      (node (ref "C21") (pin "2") (pinfunction "2_2") (pintype "passive"))
      (node (ref "U5") (pin "4") (pinfunction "BYP_4") (pintype "power_in"))
    )
    (net (code "59") (name "Net-(U6-REGOUT)") (class "Default")
      (node (ref "C12") (pin "2") (pinfunction "2_2") (pintype "passive"))
      (node (ref "U6") (pin "10") (pinfunction "REGOUT_10") (pintype "power_in"))
    )
    (net (code "60") (name "Net-(U8-BYP)") (class "Default")
      (node (ref "C13") (pin "2") (pinfunction "2_2") (pintype "passive"))
      (node (ref "U8") (pin "4") (pinfunction "BYP_4") (pintype "power_in"))
    )
    (net (code "61") (name "VM") (class "Default")
      (node (ref "C2") (pin "2") (pinfunction "2_2") (pintype "passive"))
      (node (ref "C22") (pin "2") (pinfunction "2_2") (pintype "passive"))
      (node (ref "C4") (pin "2") (pinfunction "2_2") (pintype "passive"))
      (node (ref "D1") (pin "1") (pinfunction "A_1") (pintype "passive"))
      (node (ref "D2") (pin "1") (pinfunction "A_1") (pintype "passive"))
      (node (ref "P1") (pin "1") (pinfunction "1_1") (pintype "passive"))
      (node (ref "U2") (pin "20") (pinfunction "VSB_20") (pintype "passive"))
      (node (ref "U2") (pin "22") (pinfunction "VSA_22") (pintype "passive"))
      (node (ref "U3") (pin "20") (pinfunction "VSB_20") (pintype "passive"))
      (node (ref "U3") (pin "22") (pinfunction "VSA_22") (pintype "passive"))
      (node (ref "U8") (pin "1") (pinfunction "VIN_1") (pintype "power_in"))
      (node (ref "U8") (pin "3") (pinfunction "EN_3") (pintype "power_in"))
    )
    (net (code "62") (name "unconnected-(U1-PTB1-Pad21)") (class "Default")
      (node (ref "U1") (pin "21") (pinfunction "PTB1_21") (pintype "passive"))
    )
    (net (code "63") (name "unconnected-(U2-NC-Pad10)") (class "Default")
      (node (ref "U2") (pin "10") (pinfunction "NC_10") (pintype "passive"))
    )
    (net (code "64") (name "unconnected-(U2-NC-Pad18)") (class "Default")
      (node (ref "U2") (pin "18") (pinfunction "NC_18") (pintype "passive"))
    )
    (net (code "65") (name "unconnected-(U2-NC-Pad32)") (class "Default")
      (node (ref "U2") (pin "32") (pinfunction "NC_32") (pintype "passive"))
    )
    (net (code "66") (name "unconnected-(U2-RCPULSE-Pad11)") (class "Default")
      (node (ref "U2") (pin "11") (pinfunction "RCPULSE_11") (pintype "passive"))
    )
    (net (code "67") (name "unconnected-(U3-NC-Pad10)") (class "Default")
      (node (ref "U3") (pin "10") (pinfunction "NC_10") (pintype "passive"))
    )
    (net (code "68") (name "unconnected-(U3-NC-Pad18)") (class "Default")
      (node (ref "U3") (pin "18") (pinfunction "NC_18") (pintype "passive"))
    )
    (net (code "69") (name "unconnected-(U3-NC-Pad32)") (class "Default")
      (node (ref "U3") (pin "32") (pinfunction "NC_32") (pintype "passive"))
    )
    (net (code "70") (name "unconnected-(U3-RCPULSE-Pad11)") (class "Default")
      (node (ref "U3") (pin "11") (pinfunction "RCPULSE_11") (pintype "passive"))
    )
    (net (code "71") (name "unconnected-(U6-AD0{slash}SDO-Pad9)") (class "Default")
      (node (ref "U6") (pin "9") (pinfunction "AD0/SDO_9") (pintype "power_in"))
    )
    (net (code "72") (name "unconnected-(U6-AUX_CL-Pad7)") (class "Default")
      (node (ref "U6") (pin "7") (pinfunction "AUX_CL_7") (pintype "power_in+no_connect"))
    )
    (net (code "73") (name "unconnected-(U6-AUX_DA-Pad21)") (class "Default")
      (node (ref "U6") (pin "21") (pinfunction "AUX_DA_21") (pintype "power_in+no_connect"))
    )
    (net (code "74") (name "unconnected-(U6-NC-Pad2)") (class "Default")
      (node (ref "U6") (pin "2") (pinfunction "NC_2") (pintype "power_in+no_connect"))
    )
    (net (code "75") (name "unconnected-(U6-NC-Pad3)") (class "Default")
      (node (ref "U6") (pin "3") (pinfunction "NC_3") (pintype "power_in+no_connect"))
    )
    (net (code "76") (name "unconnected-(U6-NC-Pad4)") (class "Default")
      (node (ref "U6") (pin "4") (pinfunction "NC_4") (pintype "power_in+no_connect"))
    )
    (net (code "77") (name "unconnected-(U6-NC-Pad5)") (class "Default")
      (node (ref "U6") (pin "5") (pinfunction "NC_5") (pintype "power_in+no_connect"))
    )
    (net (code "78") (name "unconnected-(U6-NC-Pad6)") (class "Default")
      (node (ref "U6") (pin "6") (pinfunction "NC_6") (pintype "power_in+no_connect"))
    )
    (net (code "79") (name "unconnected-(U6-NC-Pad14)") (class "Default")
      (node (ref "U6") (pin "14") (pinfunction "NC_14") (pintype "power_in+no_connect"))
    )
    (net (code "80") (name "unconnected-(U6-NC-Pad15)") (class "Default")
      (node (ref "U6") (pin "15") (pinfunction "NC_15") (pintype "power_in+no_connect"))
    )
    (net (code "81") (name "unconnected-(U6-NC-Pad16)") (class "Default")
      (node (ref "U6") (pin "16") (pinfunction "NC_16") (pintype "power_in+no_connect"))
    )
    (net (code "82") (name "unconnected-(U6-NC-Pad17)") (class "Default")
      (node (ref "U6") (pin "17") (pinfunction "NC_17") (pintype "power_in+no_connect"))
    )
    (net (code "83") (name "unconnected-(U6-RESV-Pad19)") (class "Default")
      (node (ref "U6") (pin "19") (pinfunction "RESV_19") (pintype "power_in+no_connect"))
    )
  )
)
